# DrVetinariClock.net
KiCad netlist of a schematic drawn in EAGLE
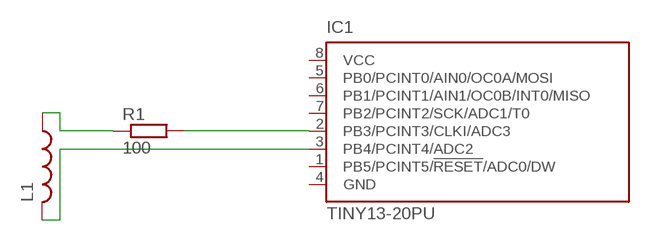
[diagram p0: schematic, sheet 1]

(export (version "E")
  (design (tool "Eeschema 10.0.6"))
  (components
    (comp (ref "IC1")
      (value "TINY13-20PU")
      (footprint "eagle-import:DIL08")
      (fields (field (name "MPN") "ATTINY13-20PU"))
      (libsource (lib "eagle-import") (part "TINY13PU-20"))
    )
    (comp (ref "L1")
      (value "L-US0204/7")
      (footprint "eagle-import:0204_7")
      (libsource (lib "eagle-import") (part "L-US0204/7"))
    )
    (comp (ref "R1")
      (value "100")
      (footprint "eagle-import:0204_7")
      (libsource (lib "eagle-import") (part "R-EU_0204/7"))
    )
  )
  (nets
    (net (code "1") (name "/GND") (class "Default")
      (node (ref "IC1") (pin "4") (pinfunction "GND_4") (pintype "power_in"))
    )
    (net (code "2") (name "/VCC") (class "Default")
      (node (ref "IC1") (pin "8") (pinfunction "VCC_8") (pintype "power_in"))
    )
    (net (code "3") (name "Net-(IC1-PB3{slash}PCINT3{slash}CLKI{slash}ADC3)") (class "Default")
      (node (ref "IC1") (pin "2") (pinfunction "PB3/PCINT3/CLKI/ADC3_2") (pintype "bidirectional"))
      (node (ref "R1") (pin "2") (pinfunction "2_2") (pintype "passive"))
    )
    (net (code "4") (name "Net-(IC1-PB4{slash}PCINT4{slash}ADC2)") (class "Default")
      (node (ref "IC1") (pin "3") (pinfunction "PB4/PCINT4/ADC2_3") (pintype "bidirectional"))
      (node (ref "L1") (pin "2") (pinfunction "2_2") (pintype "passive"))
    )
    (net (code "5") (name "Net-(L1-Pad1)") (class "Default")
      (node (ref "L1") (pin "1") (pinfunction "1_1") (pintype "passive"))
      (node (ref "R1") (pin "1") (pinfunction "1_1") (pintype "passive"))
    )
    (net (code "6") (name "unconnected-(IC1-PB0{slash}PCINT0{slash}AIN0{slash}OC0A{slash}MOSI-Pad5)") (class "Default")
      (node (ref "IC1") (pin "5") (pinfunction "PB0/PCINT0/AIN0/OC0A/MOSI_5") (pintype "bidirectional"))
    )
    (net (code "7") (name "unconnected-(IC1-PB1{slash}PCINT1{slash}AIN1{slash}OC0B{slash}INT0{slash}MISO-Pad6)") (class "Default")
      (node (ref "IC1") (pin "6") (pinfunction "PB1/PCINT1/AIN1/OC0B/INT0/MISO_6") (pintype "bidirectional"))
    )
    (net (code "8") (name "unconnected-(IC1-PB2{slash}PCINT2{slash}SCK{slash}ADC1{slash}T0-Pad7)") (class "Default")
      (node (ref "IC1") (pin "7") (pinfunction "PB2/PCINT2/SCK/ADC1/T0_7") (pintype "bidirectional"))
    )
    (net (code "9") (name "unconnected-(IC1-PB5{slash}PCINT5{slash}~{RESET}{slash}ADC0{slash}DW-Pad1)") (class "Default")
      (node (ref "IC1") (pin "1") (pinfunction "PB5/PCINT5/~{RESET}/ADC0/DW_1") (pintype "bidirectional"))
    )
  )
)
